# Sch_Dr_LC.net
KiCad netlist of a schematic drawn in Altium Designer
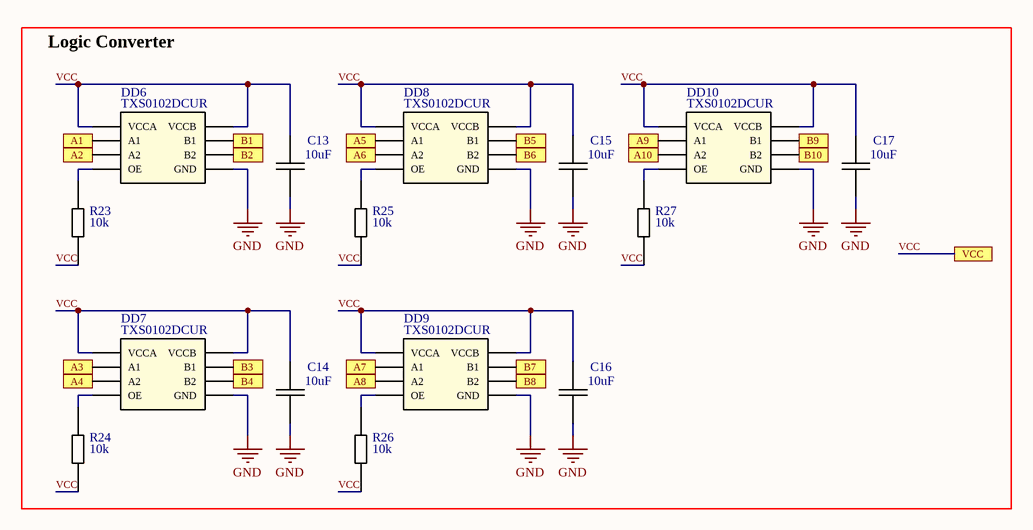
[diagram p0: Sch_Dr_LC .SchDoc]

(export (version "E")
  (design (tool "Eeschema 10.0.6"))
  (components
    (comp (ref "C13")
      (value "10uF")
      (footprint "Cap_0603")
      (description "CC0603KRX5R7BB106")
      (libsource (lib "Dr_lib") (part "Cap_"))
    )
    (comp (ref "C14")
      (value "10uF")
      (footprint "Cap_0603")
      (description "CC0603KRX5R7BB106")
      (libsource (lib "Dr_lib") (part "Cap_"))
    )
    (comp (ref "C15")
      (value "10uF")
      (footprint "Cap_0603")
      (description "CC0603KRX5R7BB106")
      (libsource (lib "Dr_lib") (part "Cap_"))
    )
    (comp (ref "C16")
      (value "10uF")
      (footprint "Cap_0603")
      (description "CC0603KRX5R7BB106")
      (libsource (lib "Dr_lib") (part "Cap_"))
    )
    (comp (ref "C17")
      (value "10uF")
      (footprint "Cap_0603")
      (description "CC0603KRX5R7BB106")
      (libsource (lib "Dr_lib") (part "Cap_"))
    )
    (comp (ref "DD6")
      (value "TXS0102DCUR")
      (footprint "VSSOP-8")
      (description "2-bit Bidirectional Voltage-level Translator for Open-Drain and Push-Pull Application")
      (libsource (lib "Dr_lib") (part "TXS0102YZ"))
    )
    (comp (ref "DD7")
      (value "TXS0102DCUR")
      (footprint "VSSOP-8")
      (description "2-bit Bidirectional Voltage-level Translator for Open-Drain and Push-Pull Application")
      (libsource (lib "Dr_lib") (part "TXS0102YZ"))
    )
    (comp (ref "DD8")
      (value "TXS0102DCUR")
      (footprint "VSSOP-8")
      (description "2-bit Bidirectional Voltage-level Translator for Open-Drain and Push-Pull Application")
      (libsource (lib "Dr_lib") (part "TXS0102YZ"))
    )
    (comp (ref "DD9")
      (value "TXS0102DCUR")
      (footprint "VSSOP-8")
      (description "2-bit Bidirectional Voltage-level Translator for Open-Drain and Push-Pull Application")
      (libsource (lib "Dr_lib") (part "TXS0102YZ"))
    )
    (comp (ref "DD10")
      (value "TXS0102DCUR")
      (footprint "VSSOP-8")
      (description "2-bit Bidirectional Voltage-level Translator for Open-Drain and Push-Pull Application")
      (libsource (lib "Dr_lib") (part "TXS0102YZ"))
    )
    (comp (ref "R23")
      (value "10k")
      (footprint "Res_0603")
      (description "CR-03FL7---10K")
      (libsource (lib "Dr_lib") (part "Res_"))
    )
    (comp (ref "R24")
      (value "10k")
      (footprint "Res_0603")
      (description "CR-03FL7---10K")
      (libsource (lib "Dr_lib") (part "Res_"))
    )
    (comp (ref "R25")
      (value "10k")
      (footprint "Res_0603")
      (description "CR-03FL7---10K")
      (libsource (lib "Dr_lib") (part "Res_"))
    )
    (comp (ref "R26")
      (value "10k")
      (footprint "Res_0603")
      (description "CR-03FL7---10K")
      (libsource (lib "Dr_lib") (part "Res_"))
    )
    (comp (ref "R27")
      (value "10k")
      (footprint "Res_0603")
      (description "CR-03FL7---10K")
      (libsource (lib "Dr_lib") (part "Res_"))
    )
  )
  (nets
    (net (code "1") (name "/A1") (class "Default")
      (node (ref "DD6") (pin "5") (pinfunction "A1_5") (pintype "passive"))
    )
    (net (code "2") (name "/A2") (class "Default")
      (node (ref "DD6") (pin "4") (pinfunction "A2_4") (pintype "passive"))
    )
    (net (code "3") (name "/A3") (class "Default")
      (node (ref "DD7") (pin "5") (pinfunction "A1_5") (pintype "passive"))
    )
    (net (code "4") (name "/A4") (class "Default")
      (node (ref "DD7") (pin "4") (pinfunction "A2_4") (pintype "passive"))
    )
    (net (code "5") (name "/A5") (class "Default")
      (node (ref "DD8") (pin "5") (pinfunction "A1_5") (pintype "passive"))
    )
    (net (code "6") (name "/A6") (class "Default")
      (node (ref "DD8") (pin "4") (pinfunction "A2_4") (pintype "passive"))
    )
    (net (code "7") (name "/A7") (class "Default")
      (node (ref "DD9") (pin "5") (pinfunction "A1_5") (pintype "passive"))
    )
    (net (code "8") (name "/A8") (class "Default")
      (node (ref "DD9") (pin "4") (pinfunction "A2_4") (pintype "passive"))
    )
    (net (code "9") (name "/A9") (class "Default")
      (node (ref "DD10") (pin "5") (pinfunction "A1_5") (pintype "passive"))
    )
    (net (code "10") (name "/A10") (class "Default")
      (node (ref "DD10") (pin "4") (pinfunction "A2_4") (pintype "passive"))
    )
    (net (code "11") (name "/B1") (class "Default")
      (node (ref "DD6") (pin "8") (pinfunction "B1_8") (pintype "passive"))
    )
    (net (code "12") (name "/B2") (class "Default")
      (node (ref "DD6") (pin "1") (pinfunction "B2_1") (pintype "passive"))
    )
    (net (code "13") (name "/B3") (class "Default")
      (node (ref "DD7") (pin "8") (pinfunction "B1_8") (pintype "passive"))
    )
    (net (code "14") (name "/B4") (class "Default")
      (node (ref "DD7") (pin "1") (pinfunction "B2_1") (pintype "passive"))
    )
    (net (code "15") (name "/B5") (class "Default")
      (node (ref "DD8") (pin "8") (pinfunction "B1_8") (pintype "passive"))
    )
    (net (code "16") (name "/B6") (class "Default")
      (node (ref "DD8") (pin "1") (pinfunction "B2_1") (pintype "passive"))
    )
    (net (code "17") (name "/B7") (class "Default")
      (node (ref "DD9") (pin "8") (pinfunction "B1_8") (pintype "passive"))
    )
    (net (code "18") (name "/B8") (class "Default")
      (node (ref "DD9") (pin "1") (pinfunction "B2_1") (pintype "passive"))
    )
    (net (code "19") (name "/B9") (class "Default")
      (node (ref "DD10") (pin "8") (pinfunction "B1_8") (pintype "passive"))
    )
    (net (code "20") (name "/B10") (class "Default")
      (node (ref "DD10") (pin "1") (pinfunction "B2_1") (pintype "passive"))
    )
    (net (code "21") (name "/VCC") (class "Default")
      (node (ref "C13") (pin "2") (pinfunction "2_2") (pintype "passive"))
      (node (ref "C14") (pin "2") (pinfunction "2_2") (pintype "passive"))
      (node (ref "C15") (pin "2") (pinfunction "2_2") (pintype "passive"))
      (node (ref "C16") (pin "2") (pinfunction "2_2") (pintype "passive"))
      (node (ref "C17") (pin "2") (pinfunction "2_2") (pintype "passive"))
      (node (ref "DD10") (pin "3") (pinfunction "VCCA_3") (pintype "passive"))
      (node (ref "DD10") (pin "7") (pinfunction "VCCB_7") (pintype "passive"))
      (node (ref "DD6") (pin "3") (pinfunction "VCCA_3") (pintype "passive"))
      (node (ref "DD6") (pin "7") (pinfunction "VCCB_7") (pintype "passive"))
      (node (ref "DD7") (pin "3") (pinfunction "VCCA_3") (pintype "passive"))
      (node (ref "DD7") (pin "7") (pinfunction "VCCB_7") (pintype "passive"))
      (node (ref "DD8") (pin "3") (pinfunction "VCCA_3") (pintype "passive"))
      (node (ref "DD8") (pin "7") (pinfunction "VCCB_7") (pintype "passive"))
      (node (ref "DD9") (pin "3") (pinfunction "VCCA_3") (pintype "passive"))
      (node (ref "DD9") (pin "7") (pinfunction "VCCB_7") (pintype "passive"))
      (node (ref "R23") (pin "2") (pinfunction "2_2") (pintype "passive"))
      (node (ref "R24") (pin "2") (pinfunction "2_2") (pintype "passive"))
      (node (ref "R25") (pin "2") (pinfunction "2_2") (pintype "passive"))
      (node (ref "R26") (pin "2") (pinfunction "2_2") (pintype "passive"))
      (node (ref "R27") (pin "2") (pinfunction "2_2") (pintype "passive"))
    )
    (net (code "22") (name "GND") (class "Default")
      (node (ref "C13") (pin "1") (pinfunction "1_1") (pintype "passive"))
      (node (ref "C14") (pin "1") (pinfunction "1_1") (pintype "passive"))
      (node (ref "C15") (pin "1") (pinfunction "1_1") (pintype "passive"))
      (node (ref "C16") (pin "1") (pinfunction "1_1") (pintype "passive"))
      (node (ref "C17") (pin "1") (pinfunction "1_1") (pintype "passive"))
      (node (ref "DD10") (pin "2") (pinfunction "GND_2") (pintype "passive"))
      (node (ref "DD6") (pin "2") (pinfunction "GND_2") (pintype "passive"))
      (node (ref "DD7") (pin "2") (pinfunction "GND_2") (pintype "passive"))
      (node (ref "DD8") (pin "2") (pinfunction "GND_2") (pintype "passive"))
      (node (ref "DD9") (pin "2") (pinfunction "GND_2") (pintype "passive"))
    )
    (net (code "23") (name "Net-(DD6-OE)") (class "Default")
      (node (ref "DD6") (pin "6") (pinfunction "OE_6") (pintype "passive"))
      (node (ref "R23") (pin "1") (pinfunction "1_1") (pintype "passive"))
    )
    (net (code "24") (name "Net-(DD7-OE)") (class "Default")
      (node (ref "DD7") (pin "6") (pinfunction "OE_6") (pintype "passive"))
      (node (ref "R24") (pin "1") (pinfunction "1_1") (pintype "passive"))
    )
    (net (code "25") (name "Net-(DD8-OE)") (class "Default")
      (node (ref "DD8") (pin "6") (pinfunction "OE_6") (pintype "passive"))
      (node (ref "R25") (pin "1") (pinfunction "1_1") (pintype "passive"))
    )
    (net (code "26") (name "Net-(DD9-OE)") (class "Default")
      (node (ref "DD9") (pin "6") (pinfunction "OE_6") (pintype "passive"))
      (node (ref "R26") (pin "1") (pinfunction "1_1") (pintype "passive"))
    )
    (net (code "27") (name "Net-(DD10-OE)") (class "Default")
      (node (ref "DD10") (pin "6") (pinfunction "OE_6") (pintype "passive"))
      (node (ref "R27") (pin "1") (pinfunction "1_1") (pintype "passive"))
    )
  )
)
